# ShiftIn-small.net
KiCad netlist of a schematic drawn in EAGLE
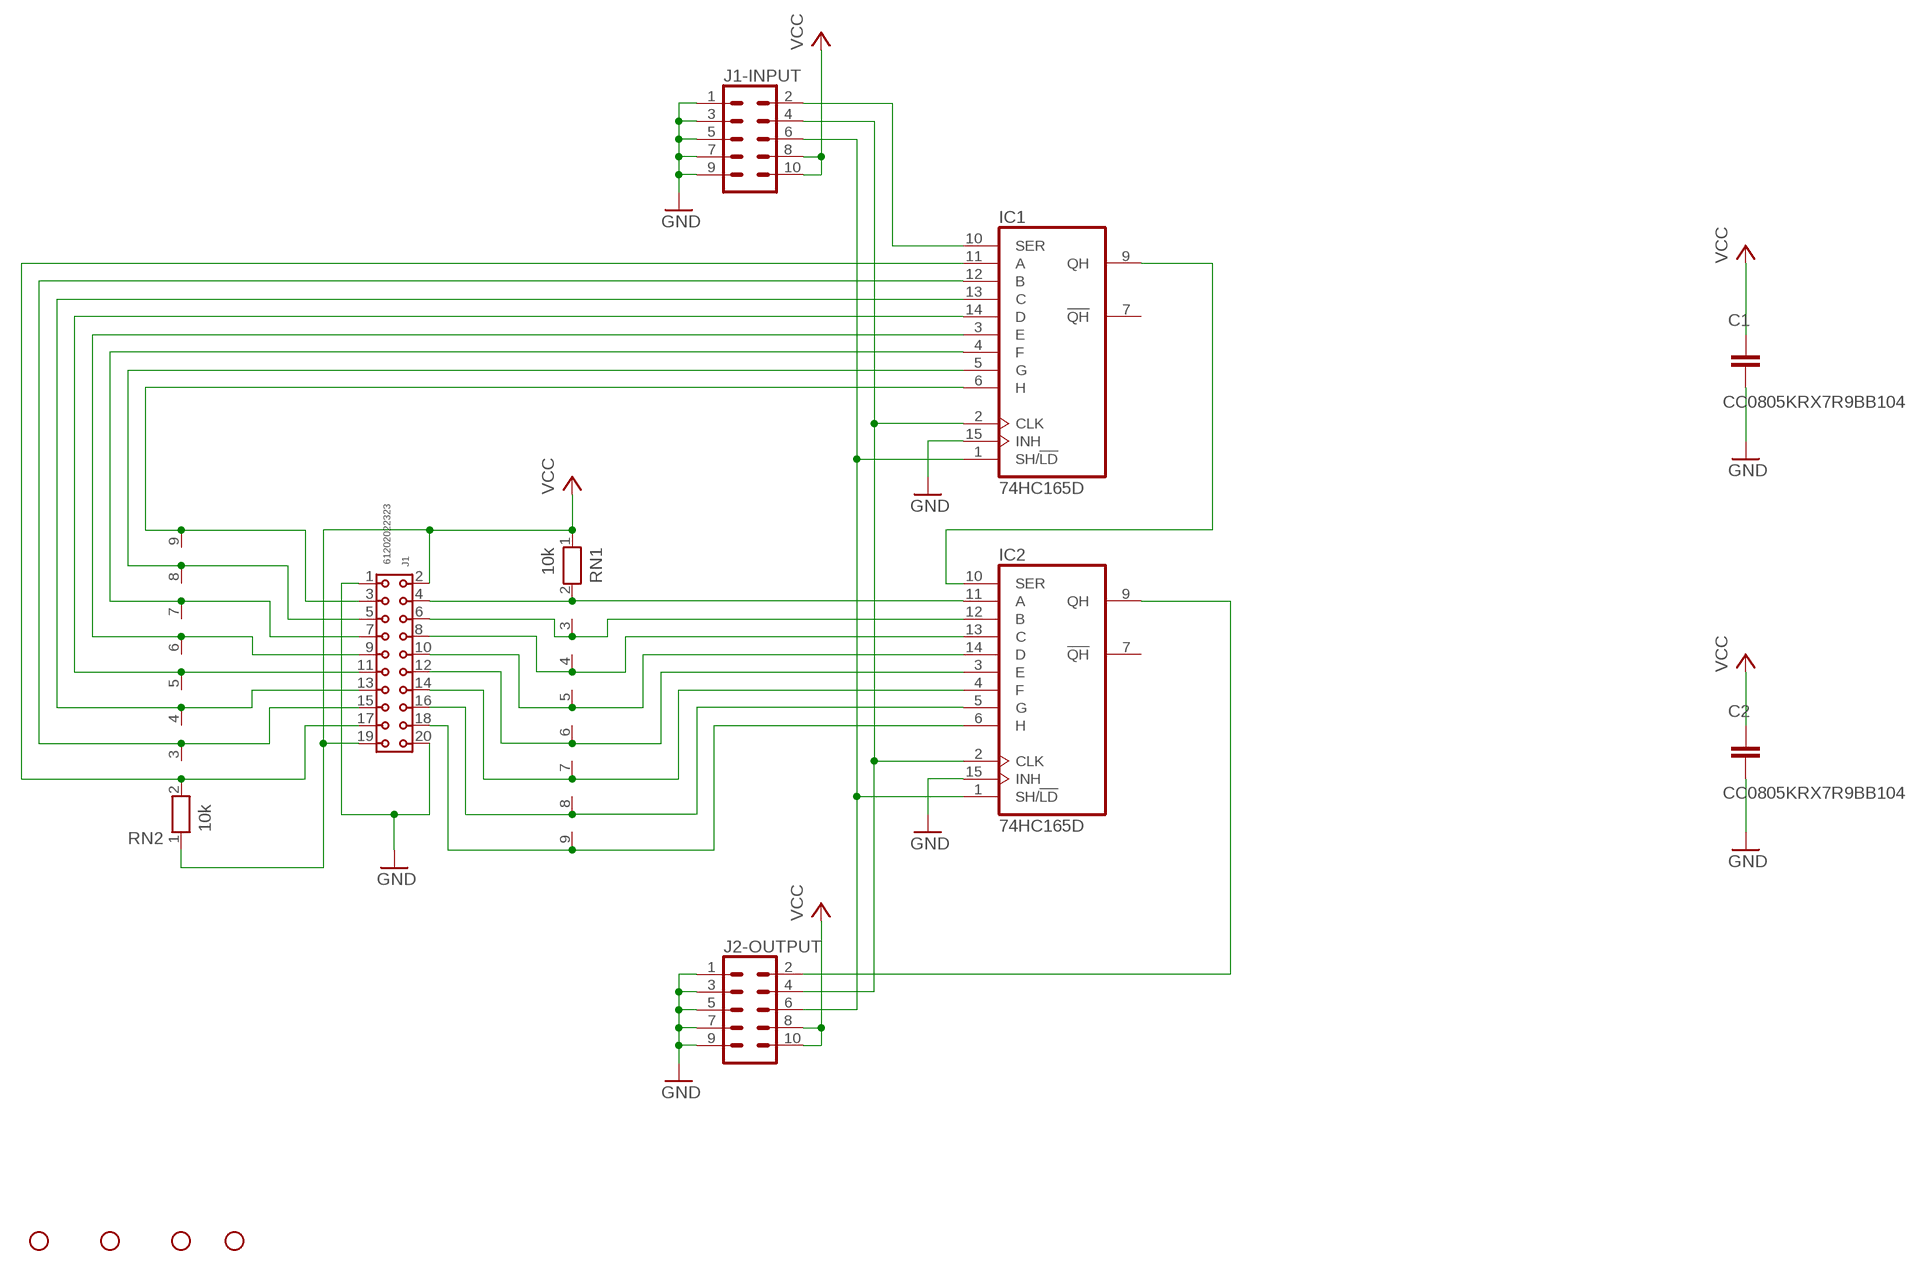
[diagram p0: schematic, sheet 1]

(export (version "E")
  (design (tool "Eeschema 10.0.6"))
  (components
    (comp (ref "C1")
      (value "CC0805KRX7R9BB104")
      (footprint "eagle-import:CAP_0805")
      (fields
        (field (name "DIGIKEY_PART_NUMBER") "311-1140-2-ND")
        (field (name "MANUFACTURER") "Yageo")
        (field (name "CREATED_BY") "PCBLayout.com")
      )
      (libsource (lib "eagle-import") (part "CC0805KRX7R9BB104"))
    )
    (comp (ref "C2")
      (value "CC0805KRX7R9BB104")
      (footprint "eagle-import:CAP_0805")
      (fields
        (field (name "DIGIKEY_PART_NUMBER") "311-1140-2-ND")
        (field (name "MANUFACTURER") "Yageo")
        (field (name "CREATED_BY") "PCBLayout.com")
      )
      (libsource (lib "eagle-import") (part "CC0805KRX7R9BB104"))
    )
    (comp (ref "H1")
      (value "STAND-OFF")
      (footprint "eagle-import:STAND-OFF")
      (libsource (lib "eagle-import") (part "STAND-OFF"))
    )
    (comp (ref "H2")
      (value "STAND-OFF")
      (footprint "eagle-import:STAND-OFF")
      (libsource (lib "eagle-import") (part "STAND-OFF"))
    )
    (comp (ref "H3")
      (value "STAND-OFF")
      (footprint "eagle-import:STAND-OFF")
      (libsource (lib "eagle-import") (part "STAND-OFF"))
    )
    (comp (ref "H4")
      (value "STAND-OFF")
      (footprint "eagle-import:STAND-OFF")
      (libsource (lib "eagle-import") (part "STAND-OFF"))
    )
    (comp (ref "IC1")
      (value "74HC165D")
      (footprint "eagle-import:SO16")
      (libsource (lib "eagle-import") (part "74165DHC"))
    )
    (comp (ref "IC2")
      (value "74HC165D")
      (footprint "eagle-import:SO16")
      (libsource (lib "eagle-import") (part "74165DHC"))
    )
    (comp (ref "J1")
      (value "61202022323")
      (footprint "eagle-import:61202022323")
      (libsource (lib "eagle-import") (part "6120XX22323_61202022323"))
    )
    (comp (ref "J1-INPUT")
      (value "CONN_05X2SHD_LOCK")
      (footprint "eagle-import:2X5-SHROUDED_LOCK")
      (libsource (lib "eagle-import") (part "CONN_05X2SHD_LOCK"))
    )
    (comp (ref "J2-OUTPUT")
      (value "CONN_05X2SHD_LOCK")
      (footprint "eagle-import:2X5-SHROUDED_LOCK")
      (libsource (lib "eagle-import") (part "CONN_05X2SHD_LOCK"))
    )
    (comp (ref "RN1")
      (value "10k")
      (footprint "eagle-import:RN-9")
      (libsource (lib "eagle-import") (part "RN08"))
    )
    (comp (ref "RN2")
      (value "10k")
      (footprint "eagle-import:RN-9")
      (libsource (lib "eagle-import") (part "RN08"))
    )
  )
  (nets
    (net (code "1") (name "GND") (class "Default")
      (node (ref "C1") (pin "2") (pinfunction "2_2") (pintype "passive"))
      (node (ref "C2") (pin "2") (pinfunction "2_2") (pintype "passive"))
      (node (ref "IC1") (pin "15") (pinfunction "INH_15") (pintype "input"))
      (node (ref "IC2") (pin "15") (pinfunction "INH_15") (pintype "input"))
      (node (ref "J1") (pin "1") (pinfunction "1_1") (pintype "passive"))
      (node (ref "J1") (pin "20") (pinfunction "20_20") (pintype "passive"))
      (node (ref "J1-INPUT") (pin "1") (pinfunction "1_1") (pintype "passive"))
      (node (ref "J1-INPUT") (pin "3") (pinfunction "3_3") (pintype "passive"))
      (node (ref "J1-INPUT") (pin "5") (pinfunction "5_5") (pintype "passive"))
      (node (ref "J1-INPUT") (pin "7") (pinfunction "7_7") (pintype "passive"))
      (node (ref "J1-INPUT") (pin "9") (pinfunction "9_9") (pintype "passive"))
      (node (ref "J2-OUTPUT") (pin "1") (pinfunction "1_1") (pintype "passive"))
      (node (ref "J2-OUTPUT") (pin "3") (pinfunction "3_3") (pintype "passive"))
      (node (ref "J2-OUTPUT") (pin "5") (pinfunction "5_5") (pintype "passive"))
      (node (ref "J2-OUTPUT") (pin "7") (pinfunction "7_7") (pintype "passive"))
      (node (ref "J2-OUTPUT") (pin "9") (pinfunction "9_9") (pintype "passive"))
    )
    (net (code "2") (name "Net-(IC1A-A)") (class "Default")
      (node (ref "IC1") (pin "11") (pinfunction "A_11") (pintype "input"))
      (node (ref "J1") (pin "17") (pinfunction "17_17") (pintype "passive"))
      (node (ref "RN2") (pin "2") (pinfunction "2_2") (pintype "passive"))
    )
    (net (code "3") (name "Net-(IC1A-B)") (class "Default")
      (node (ref "IC1") (pin "12") (pinfunction "B_12") (pintype "input"))
      (node (ref "J1") (pin "15") (pinfunction "15_15") (pintype "passive"))
      (node (ref "RN2") (pin "3") (pinfunction "3_3") (pintype "passive"))
    )
    (net (code "4") (name "Net-(IC1A-C)") (class "Default")
      (node (ref "IC1") (pin "13") (pinfunction "C_13") (pintype "input"))
      (node (ref "J1") (pin "13") (pinfunction "13_13") (pintype "passive"))
      (node (ref "RN2") (pin "4") (pinfunction "4_4") (pintype "passive"))
    )
    (net (code "5") (name "Net-(IC1A-CLK)") (class "Default")
      (node (ref "IC1") (pin "2") (pinfunction "CLK_2") (pintype "input"))
      (node (ref "IC2") (pin "2") (pinfunction "CLK_2") (pintype "input"))
      (node (ref "J1-INPUT") (pin "4") (pinfunction "4_4") (pintype "passive"))
      (node (ref "J2-OUTPUT") (pin "4") (pinfunction "4_4") (pintype "passive"))
    )
    (net (code "6") (name "Net-(IC1A-D)") (class "Default")
      (node (ref "IC1") (pin "14") (pinfunction "D_14") (pintype "input"))
      (node (ref "J1") (pin "11") (pinfunction "11_11") (pintype "passive"))
      (node (ref "RN2") (pin "5") (pinfunction "5_5") (pintype "passive"))
    )
    (net (code "7") (name "Net-(IC1A-E)") (class "Default")
      (node (ref "IC1") (pin "3") (pinfunction "E_3") (pintype "input"))
      (node (ref "J1") (pin "9") (pinfunction "9_9") (pintype "passive"))
      (node (ref "RN2") (pin "6") (pinfunction "6_6") (pintype "passive"))
    )
    (net (code "8") (name "Net-(IC1A-F)") (class "Default")
      (node (ref "IC1") (pin "4") (pinfunction "F_4") (pintype "input"))
      (node (ref "J1") (pin "7") (pinfunction "7_7") (pintype "passive"))
      (node (ref "RN2") (pin "7") (pinfunction "7_7") (pintype "passive"))
    )
    (net (code "9") (name "Net-(IC1A-G)") (class "Default")
      (node (ref "IC1") (pin "5") (pinfunction "G_5") (pintype "input"))
      (node (ref "J1") (pin "5") (pinfunction "5_5") (pintype "passive"))
      (node (ref "RN2") (pin "8") (pinfunction "8_8") (pintype "passive"))
    )
    (net (code "10") (name "Net-(IC1A-H)") (class "Default")
      (node (ref "IC1") (pin "6") (pinfunction "H_6") (pintype "input"))
      (node (ref "J1") (pin "3") (pinfunction "3_3") (pintype "passive"))
      (node (ref "RN2") (pin "9") (pinfunction "9_9") (pintype "passive"))
    )
    (net (code "11") (name "Net-(IC1A-QH)") (class "Default")
      (node (ref "IC1") (pin "9") (pinfunction "QH_9") (pintype "output"))
      (node (ref "IC2") (pin "10") (pinfunction "SER_10") (pintype "input"))
    )
    (net (code "12") (name "Net-(IC1A-SER)") (class "Default")
      (node (ref "IC1") (pin "10") (pinfunction "SER_10") (pintype "input"))
      (node (ref "J1-INPUT") (pin "2") (pinfunction "2_2") (pintype "passive"))
    )
    (net (code "13") (name "Net-(IC1A-SH{slash}~{LD})") (class "Default")
      (node (ref "IC1") (pin "1") (pinfunction "SH/~{LD}_1") (pintype "input"))
      (node (ref "IC2") (pin "1") (pinfunction "SH/~{LD}_1") (pintype "input"))
      (node (ref "J1-INPUT") (pin "6") (pinfunction "6_6") (pintype "passive"))
      (node (ref "J2-OUTPUT") (pin "6") (pinfunction "6_6") (pintype "passive"))
    )
    (net (code "14") (name "Net-(IC2A-A)") (class "Default")
      (node (ref "IC2") (pin "11") (pinfunction "A_11") (pintype "input"))
      (node (ref "J1") (pin "4") (pinfunction "4_4") (pintype "passive"))
      (node (ref "RN1") (pin "2") (pinfunction "2_2") (pintype "passive"))
    )
    (net (code "15") (name "Net-(IC2A-B)") (class "Default")
      (node (ref "IC2") (pin "12") (pinfunction "B_12") (pintype "input"))
      (node (ref "J1") (pin "6") (pinfunction "6_6") (pintype "passive"))
      (node (ref "RN1") (pin "3") (pinfunction "3_3") (pintype "passive"))
    )
    (net (code "16") (name "Net-(IC2A-C)") (class "Default")
      (node (ref "IC2") (pin "13") (pinfunction "C_13") (pintype "input"))
      (node (ref "J1") (pin "8") (pinfunction "8_8") (pintype "passive"))
      (node (ref "RN1") (pin "4") (pinfunction "4_4") (pintype "passive"))
    )
    (net (code "17") (name "Net-(IC2A-D)") (class "Default")
      (node (ref "IC2") (pin "14") (pinfunction "D_14") (pintype "input"))
      (node (ref "J1") (pin "10") (pinfunction "10_10") (pintype "passive"))
      (node (ref "RN1") (pin "5") (pinfunction "5_5") (pintype "passive"))
    )
    (net (code "18") (name "Net-(IC2A-E)") (class "Default")
      (node (ref "IC2") (pin "3") (pinfunction "E_3") (pintype "input"))
      (node (ref "J1") (pin "12") (pinfunction "12_12") (pintype "passive"))
      (node (ref "RN1") (pin "6") (pinfunction "6_6") (pintype "passive"))
    )
    (net (code "19") (name "Net-(IC2A-F)") (class "Default")
      (node (ref "IC2") (pin "4") (pinfunction "F_4") (pintype "input"))
      (node (ref "J1") (pin "14") (pinfunction "14_14") (pintype "passive"))
      (node (ref "RN1") (pin "7") (pinfunction "7_7") (pintype "passive"))
    )
    (net (code "20") (name "Net-(IC2A-G)") (class "Default")
      (node (ref "IC2") (pin "5") (pinfunction "G_5") (pintype "input"))
      (node (ref "J1") (pin "16") (pinfunction "16_16") (pintype "passive"))
      (node (ref "RN1") (pin "8") (pinfunction "8_8") (pintype "passive"))
    )
    (net (code "21") (name "Net-(IC2A-H)") (class "Default")
      (node (ref "IC2") (pin "6") (pinfunction "H_6") (pintype "input"))
      (node (ref "J1") (pin "18") (pinfunction "18_18") (pintype "passive"))
      (node (ref "RN1") (pin "9") (pinfunction "9_9") (pintype "passive"))
    )
    (net (code "22") (name "Net-(IC2A-QH)") (class "Default")
      (node (ref "IC2") (pin "9") (pinfunction "QH_9") (pintype "output"))
      (node (ref "J2-OUTPUT") (pin "2") (pinfunction "2_2") (pintype "passive"))
    )
    (net (code "23") (name "VCC") (class "Default")
      (node (ref "C1") (pin "1") (pinfunction "1_1") (pintype "passive"))
      (node (ref "C2") (pin "1") (pinfunction "1_1") (pintype "passive"))
      (node (ref "J1") (pin "19") (pinfunction "19_19") (pintype "passive"))
      (node (ref "J1") (pin "2") (pinfunction "2_2") (pintype "passive"))
      (node (ref "J1-INPUT") (pin "10") (pinfunction "10_10") (pintype "passive"))
      (node (ref "J1-INPUT") (pin "8") (pinfunction "8_8") (pintype "passive"))
      (node (ref "J2-OUTPUT") (pin "10") (pinfunction "10_10") (pintype "passive"))
      (node (ref "J2-OUTPUT") (pin "8") (pinfunction "8_8") (pintype "passive"))
      (node (ref "RN1") (pin "1") (pinfunction "1_1") (pintype "passive"))
      (node (ref "RN2") (pin "1") (pinfunction "1_1") (pintype "passive"))
    )
    (net (code "24") (name "unconnected-(IC1A-~{QH}-Pad7)") (class "Default")
      (node (ref "IC1") (pin "7") (pinfunction "~{QH}_7") (pintype "output"))
    )
    (net (code "25") (name "unconnected-(IC2A-~{QH}-Pad7)") (class "Default")
      (node (ref "IC2") (pin "7") (pinfunction "~{QH}_7") (pintype "output"))
    )
  )
)
